# main.net
KiCad netlist of a schematic drawn in Altium Designer
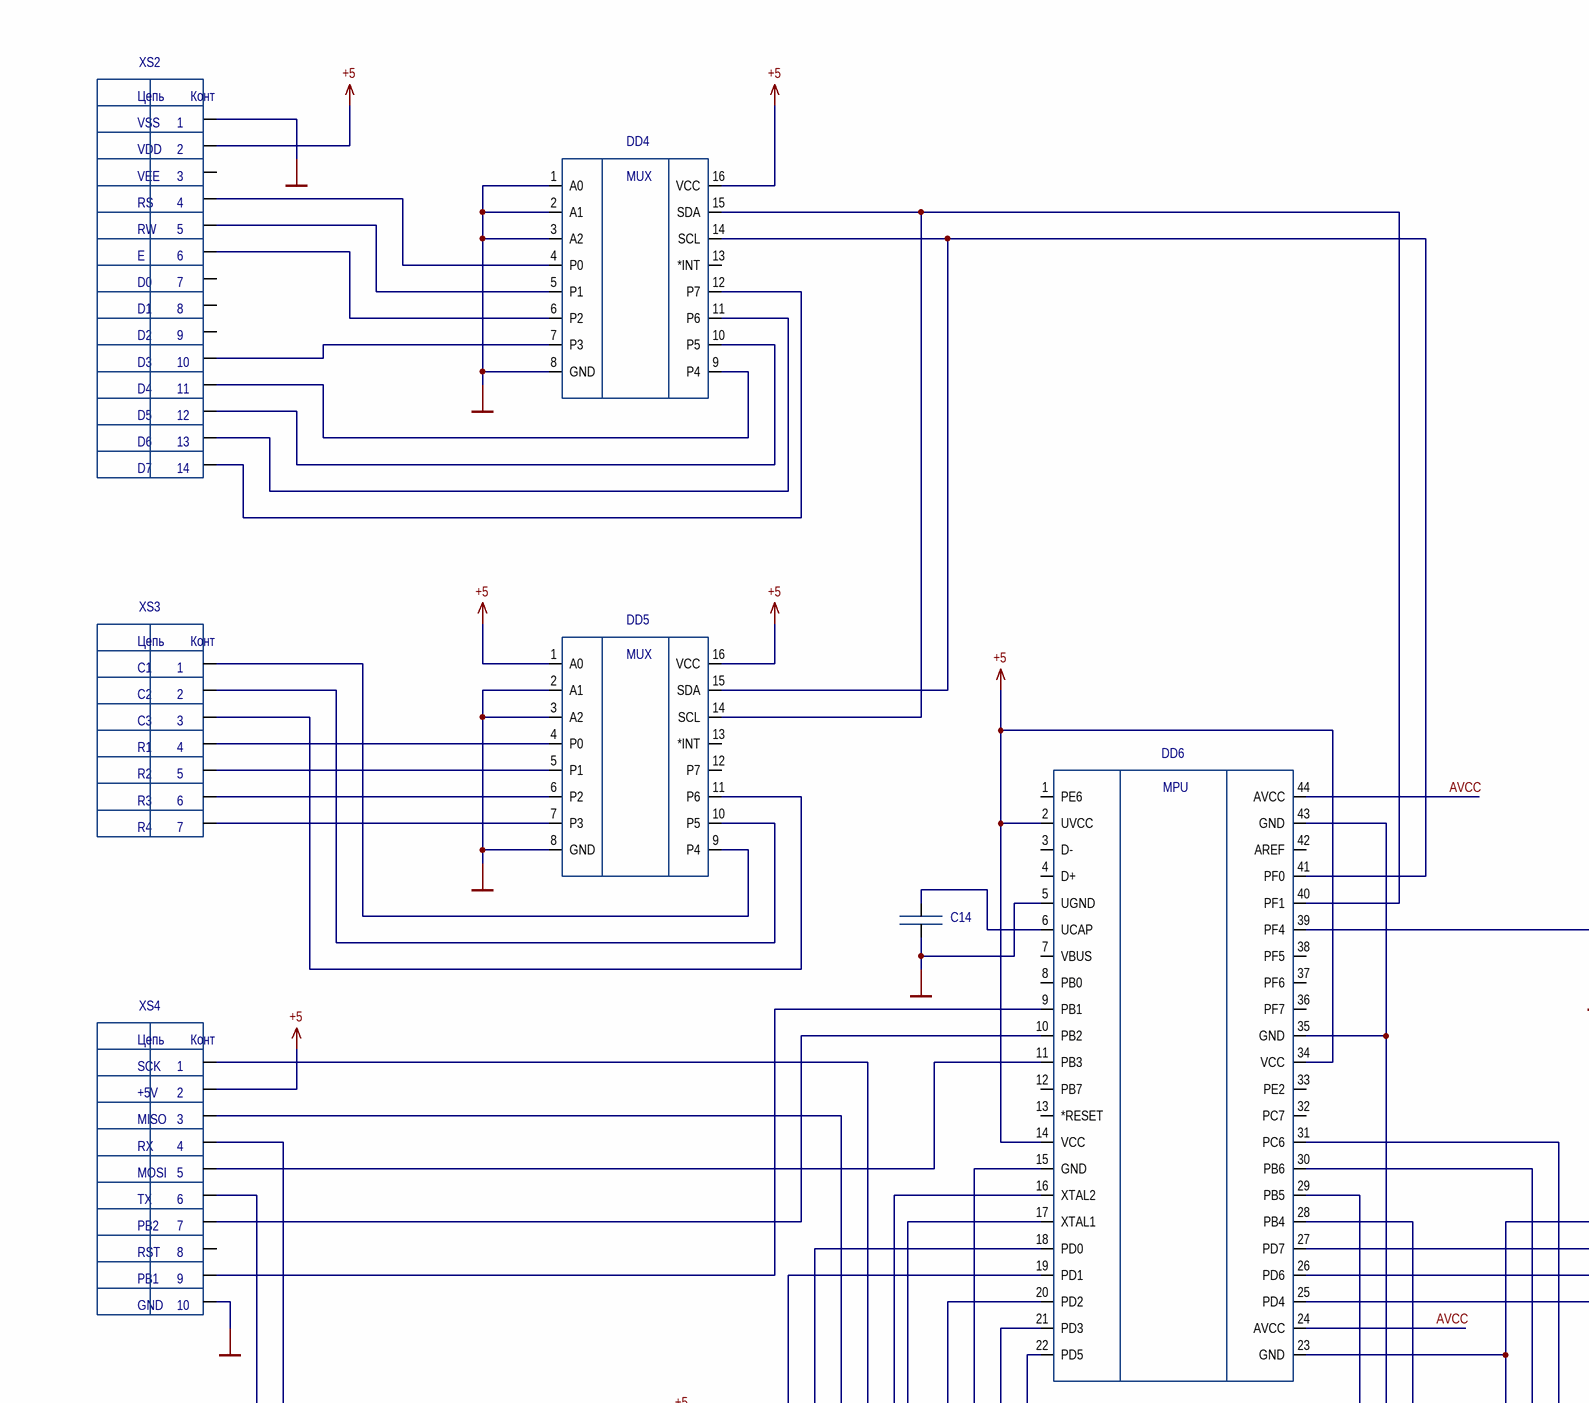
[diagram p0: main.SchDoc, top left]
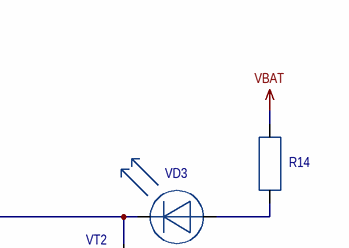
[diagram p1: main.SchDoc, top right]
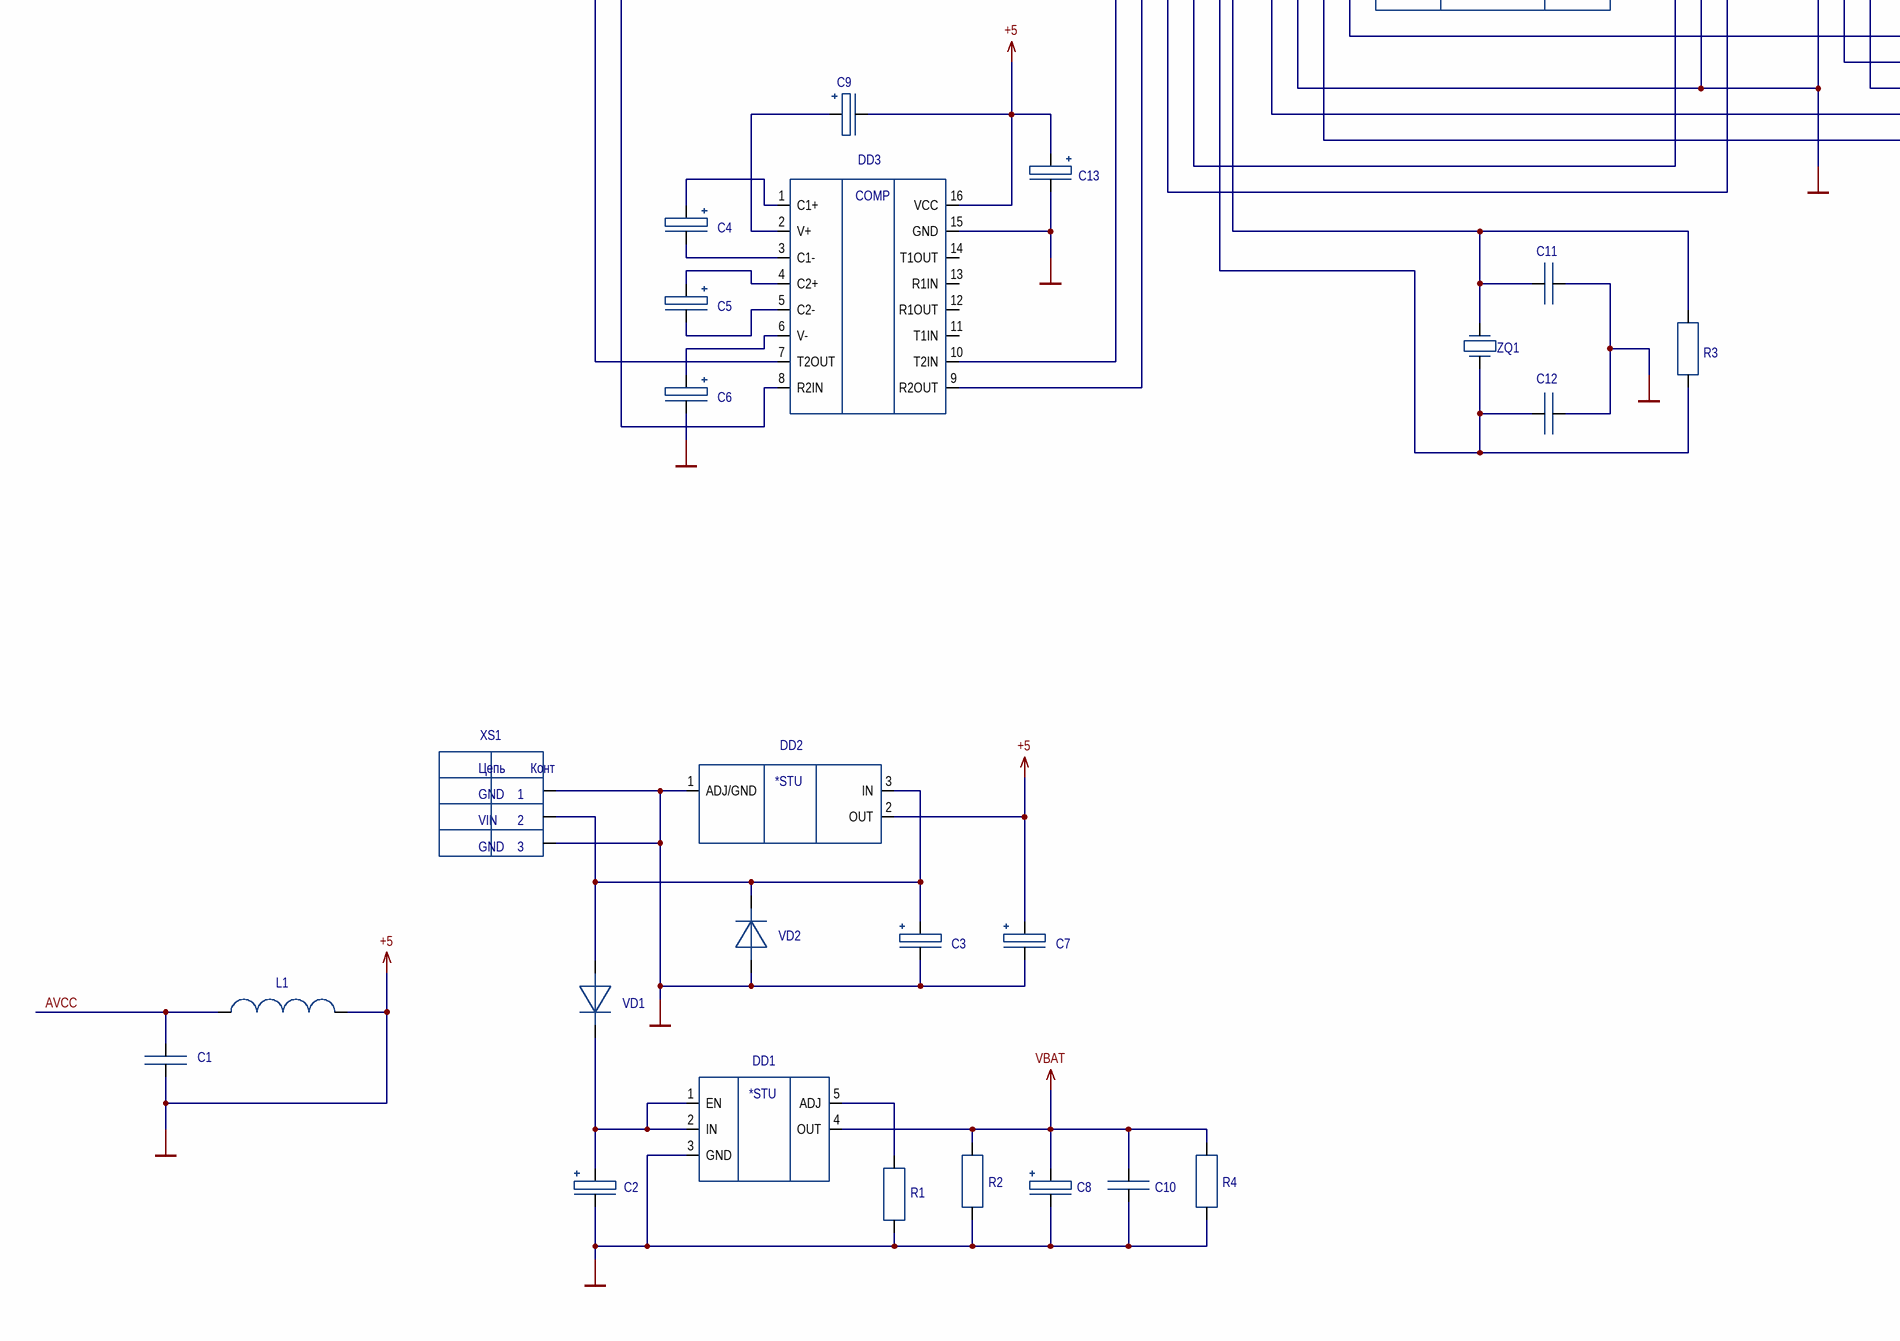
[diagram p2: main.SchDoc, bottom left]
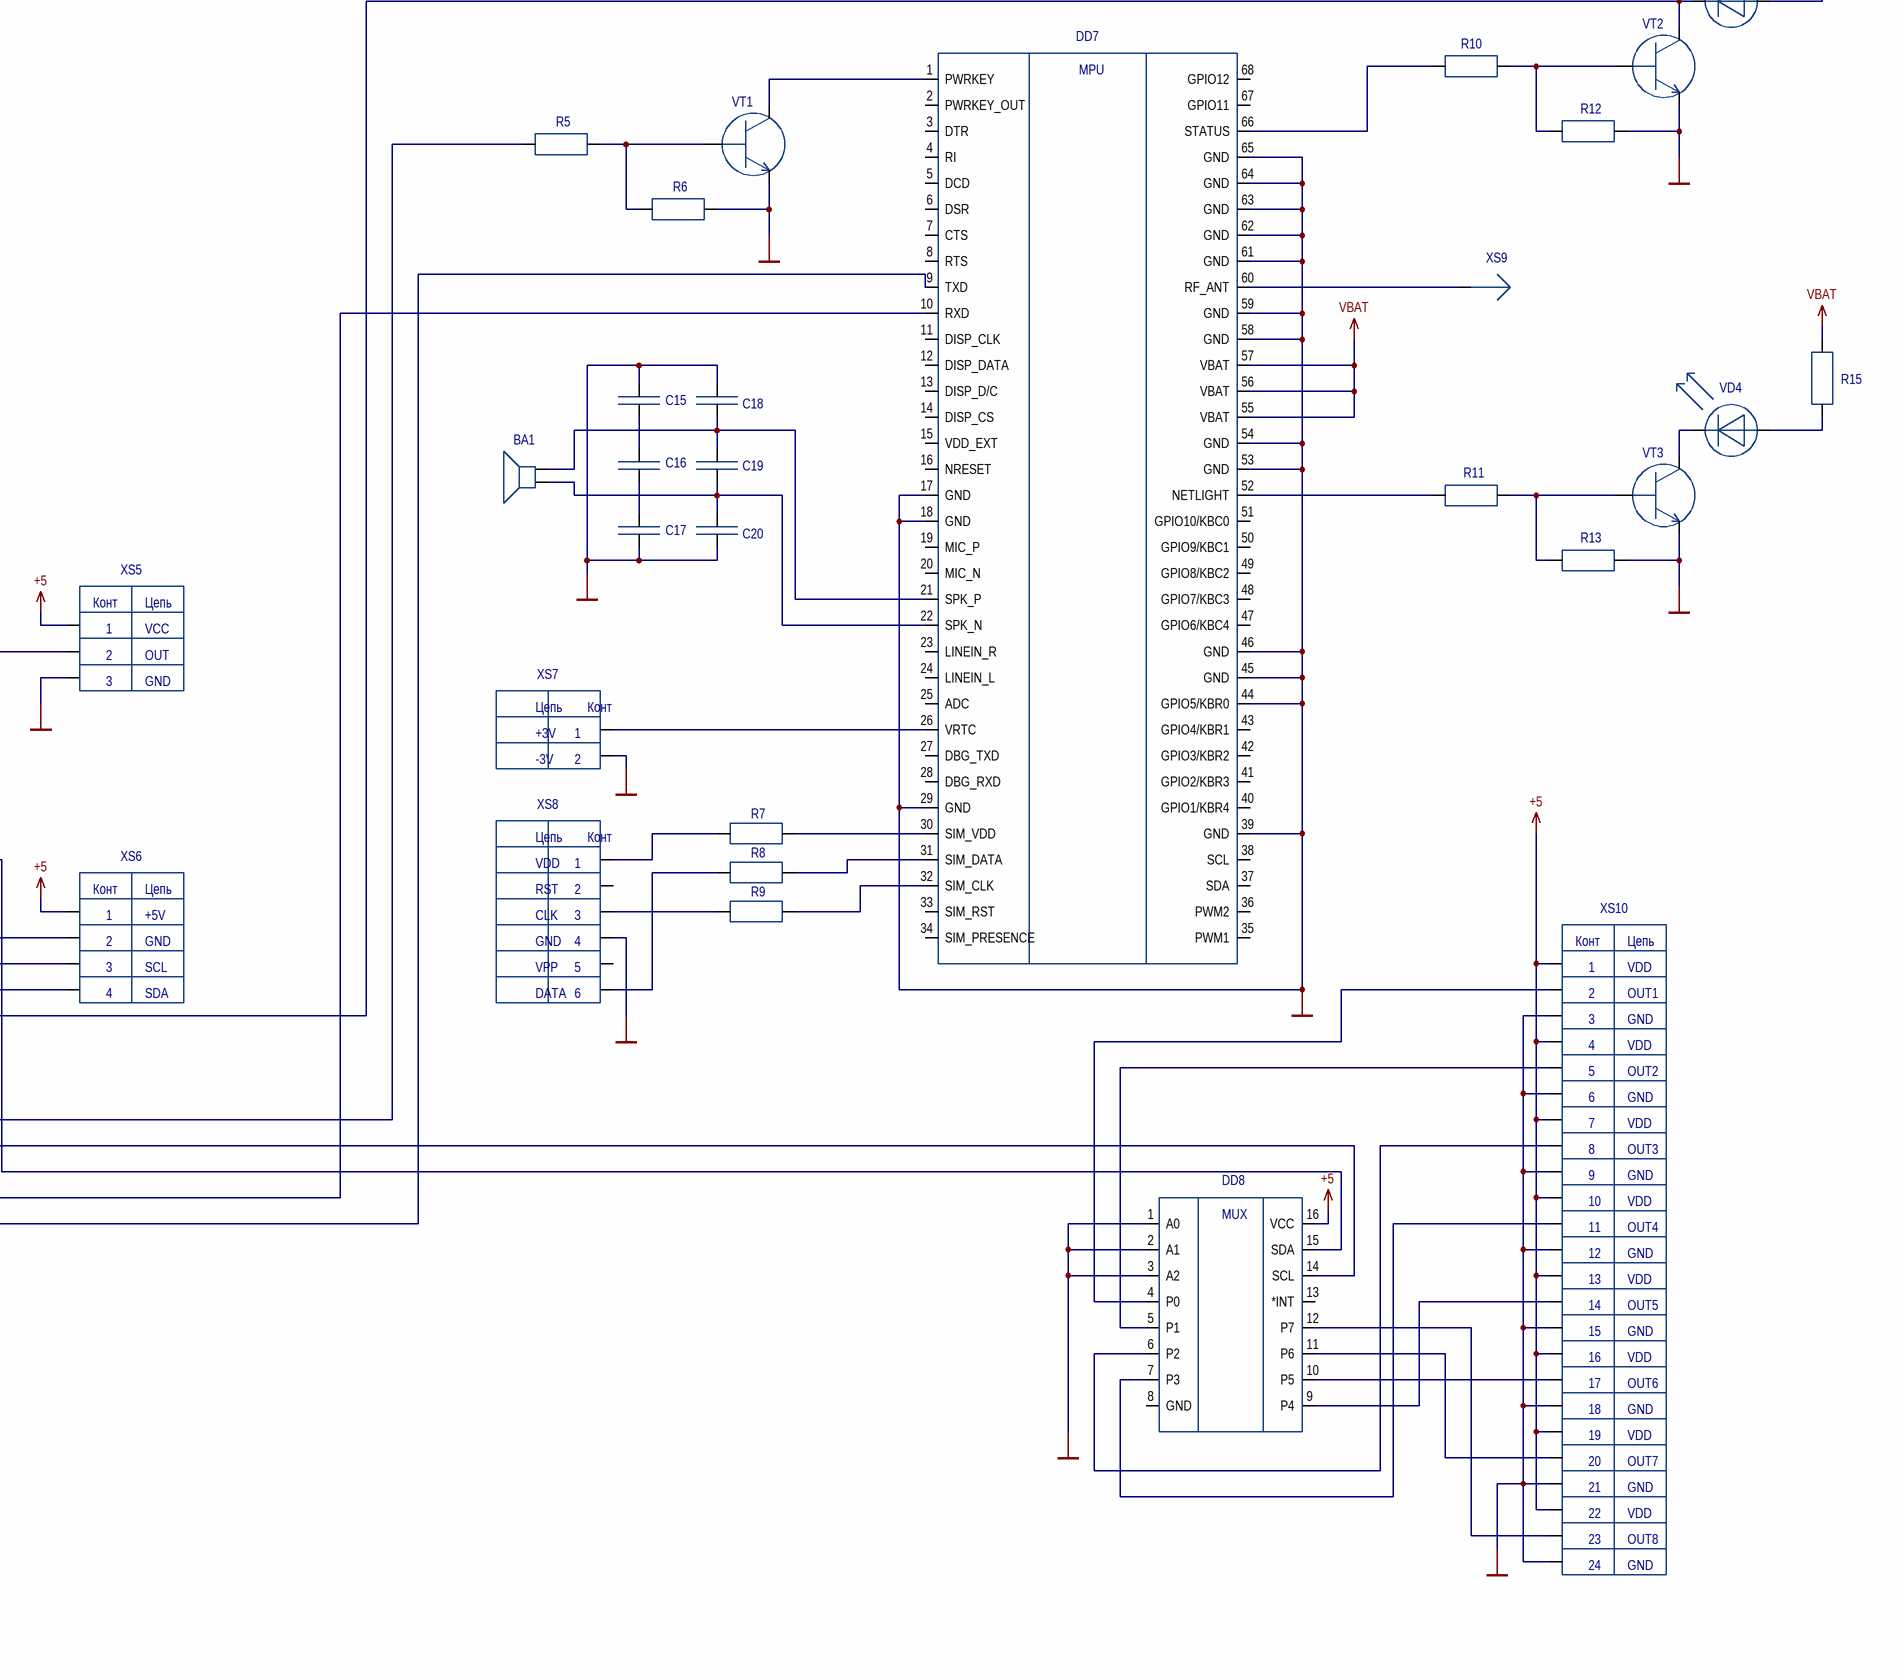
[diagram p3: main.SchDoc, bottom right]

(export (version "E")
  (design (tool "Eeschema 10.0.6"))
  (components
    (comp (ref "BA1")
      (value "speaker_CVS-1508")
      (footprint "diploma:SPeaKeR_CVS-1508")
      (libsource (lib "diploma") (part "speaker_CVS-1508"))
    )
    (comp (ref "C1")
      (value "cap_1mkF")
      (footprint "diploma:CAP_0805_GRM")
      (libsource (lib "diploma") (part "cap_1mkF"))
    )
    (comp (ref "C2")
      (value "cap_pol_100mkF")
      (footprint "diploma:PCAP_10X20_RUB")
      (libsource (lib "diploma") (part "cap_pol_100mkF"))
    )
    (comp (ref "C3")
      (value "pol_10mkF")
      (footprint "diploma:PCAP_6_3x11THRU-ELECT_NCA")
      (libsource (lib "diploma") (part "cap_pol_10mkF"))
    )
    (comp (ref "C4")
      (value "pol_1mkF")
      (footprint "PCAP_5x11-THRU-ELECT_NCA")
      (libsource (lib "diploma") (part "cap_pol_1mkF"))
    )
    (comp (ref "C5")
      (value "pol_1mkF")
      (footprint "PCAP_5x11-THRU-ELECT_NCA")
      (libsource (lib "diploma") (part "cap_pol_1mkF"))
    )
    (comp (ref "C6")
      (value "pol_1mkF")
      (footprint "PCAP_5x11-THRU-ELECT_NCA")
      (libsource (lib "diploma") (part "cap_pol_1mkF"))
    )
    (comp (ref "C7")
      (value "pol_10mkF")
      (footprint "diploma:PCAP_6_3x11THRU-ELECT_NCA")
      (libsource (lib "diploma") (part "cap_pol_10mkF"))
    )
    (comp (ref "C8")
      (value "cap_pol_100mkF")
      (footprint "diploma:PCAP_10X20_RUB")
      (libsource (lib "diploma") (part "cap_pol_100mkF"))
    )
    (comp (ref "C9")
      (value "pol_1mkF")
      (footprint "PCAP_5x11-THRU-ELECT_NCA")
      (libsource (lib "diploma") (part "cap_pol_1mkF"))
    )
    (comp (ref "C10")
      (value "cap_100nF")
      (footprint "diploma:CAP_0805_GRM")
      (libsource (lib "diploma") (part "cap_100nF"))
    )
    (comp (ref "C11")
      (value "33pF")
      (footprint "diploma:CAP_0805_GRM")
      (libsource (lib "diploma") (part "cap_33pF"))
    )
    (comp (ref "C12")
      (value "33pF")
      (footprint "diploma:CAP_0805_GRM")
      (libsource (lib "diploma") (part "cap_33pF"))
    )
    (comp (ref "C13")
      (value "pol_1mkF")
      (footprint "PCAP_5x11-THRU-ELECT_NCA")
      (libsource (lib "diploma") (part "cap_pol_1mkF"))
    )
    (comp (ref "C14")
      (value "cap_1mkF")
      (footprint "diploma:CAP_0805_GRM")
      (libsource (lib "diploma") (part "cap_1mkF"))
    )
    (comp (ref "C15")
      (value "cap_10pF")
      (footprint "CAP_0805_GRM")
      (libsource (lib "diploma") (part "cap_10pF"))
    )
    (comp (ref "C16")
      (value "cap_10pF")
      (footprint "CAP_0805_GRM")
      (libsource (lib "diploma") (part "cap_10pF"))
    )
    (comp (ref "C17")
      (value "cap_10pF")
      (footprint "CAP_0805_GRM")
      (libsource (lib "diploma") (part "cap_10pF"))
    )
    (comp (ref "C18")
      (value "cap_33pF")
      (footprint "diploma:CAP_0805_GRM")
      (libsource (lib "diploma") (part "cap_33pF"))
    )
    (comp (ref "C19")
      (value "cap_33pF")
      (footprint "diploma:CAP_0805_GRM")
      (libsource (lib "diploma") (part "cap_33pF"))
    )
    (comp (ref "C20")
      (value "cap_33pF")
      (footprint "diploma:CAP_0805_GRM")
      (libsource (lib "diploma") (part "cap_33pF"))
    )
    (comp (ref "DD1")
      (value "stu_MIC29302WT")
      (footprint "diploma:TO-263-5_MCH")
      (libsource (lib "diploma") (part "stu_MIC29302WT"))
    )
    (comp (ref "DD2")
      (value "NCP1117ST50T3G")
      (footprint "SOT223-3_ONS")
      (description "No Description Available")
      (fields (field (name "COPYRIGHT") "Copyright (C) 2016 Accelerated Designs. All rights reserved"))
      (libsource (lib "diploma") (part "stu_NCP1117ST50T3G"))
    )
    (comp (ref "DD3")
      (value "MAX232CSE+")
      (footprint "diploma:max232_dip16")
      (description "No Description Available")
      (fields (field (name "COPYRIGHT") "Copyright (C) 2018 Accelerated Designs. All rights reserved"))
      (libsource (lib "diploma") (part "micro_MAX232"))
    )
    (comp (ref "DD4")
      (value "PCF8574AP")
      (footprint "diploma:SOT38-4_NXP")
      (description "No Description Available")
      (fields (field (name "COPYRIGHT") "Copyright (C) 2018 Accelerated Designs. All rights reserved"))
      (libsource (lib "diploma") (part "micro_PCF8574AP"))
    )
    (comp (ref "DD5")
      (value "PCF8574AP")
      (footprint "diploma:SOT38-4_NXP")
      (description "No Description Available")
      (fields (field (name "COPYRIGHT") "Copyright (C) 2018 Accelerated Designs. All rights reserved"))
      (libsource (lib "diploma") (part "micro_PCF8574AP"))
    )
    (comp (ref "DD6")
      (value "ATMEGA32U4RC-AU")
      (footprint "diploma:atmega32u4_44ML_ATM")
      (description "No Description Available")
      (fields (field (name "COPYRIGHT") "Copyright (C) 2018 Accelerated Designs. All rights reserved"))
      (libsource (lib "diploma") (part "micro_ATMEGA32U4"))
    )
    (comp (ref "DD7")
      (value "SIM900A")
      (footprint "diploma:SIM800A_SMM")
      (libsource (lib "diploma") (part "SIM900A"))
    )
    (comp (ref "DD8")
      (value "PCF8574AP")
      (footprint "diploma:SOT38-4_NXP")
      (description "No Description Available")
      (fields (field (name "COPYRIGHT") "Copyright (C) 2018 Accelerated Designs. All rights reserved"))
      (libsource (lib "diploma") (part "micro_PCF8574AP"))
    )
    (comp (ref "L1")
      (value "inductor_10uH")
      (footprint "diploma:IND_EPCOS_B82432A_EPC")
      (libsource (lib "diploma") (part "inductor_10uH"))
    )
    (comp (ref "R1")
      (value "res_47k")
      (footprint "diploma:RC0805N_YAG")
      (libsource (lib "diploma") (part "res_47k"))
    )
    (comp (ref "R2")
      (value "res_100K")
      (footprint "diploma:RC0805N_YAG")
      (libsource (lib "diploma") (part "res_100K"))
    )
    (comp (ref "R3")
      (value "res_1M")
      (footprint "diploma:RC0805N_YAG")
      (libsource (lib "diploma") (part "res_1M"))
    )
    (comp (ref "R4")
      (value "res_510")
      (footprint "diploma:RC0805N_YAG")
      (libsource (lib "diploma") (part "res_510"))
    )
    (comp (ref "R5")
      (value "res_4.7k")
      (footprint "diploma:RC0805N_YAG")
      (libsource (lib "diploma") (part "res_4.7k"))
    )
    (comp (ref "R6")
      (value "res_47k")
      (footprint "diploma:RC0805N_YAG")
      (libsource (lib "") (part "res_47k_1"))
    )
    (comp (ref "R7")
      (value "res_22")
      (footprint "diploma:RC0805N_YAG")
      (libsource (lib "diploma") (part "res_22"))
    )
    (comp (ref "R8")
      (value "res_22")
      (footprint "diploma:RC0805N_YAG")
      (libsource (lib "diploma") (part "res_22"))
    )
    (comp (ref "R9")
      (value "res_22")
      (footprint "diploma:RC0805N_YAG")
      (libsource (lib "diploma") (part "res_22"))
    )
    (comp (ref "R10")
      (value "res_4.7k")
      (footprint "diploma:RC0805N_YAG")
      (libsource (lib "diploma") (part "res_4.7k"))
    )
    (comp (ref "R11")
      (value "res_4.7k")
      (footprint "diploma:RC0805N_YAG")
      (libsource (lib "diploma") (part "res_4.7k"))
    )
    (comp (ref "R12")
      (value "res_47k")
      (footprint "diploma:RC0805N_YAG")
      (libsource (lib "") (part "res_47k_1"))
    )
    (comp (ref "R13")
      (value "res_47k")
      (footprint "diploma:RC0805N_YAG")
      (libsource (lib "") (part "res_47k_1"))
    )
    (comp (ref "R14")
      (value "res_510")
      (footprint "diploma:RC0805N_YAG")
      (libsource (lib "diploma") (part "res_510"))
    )
    (comp (ref "R15")
      (value "res_510")
      (footprint "diploma:RC0805N_YAG")
      (libsource (lib "diploma") (part "res_510"))
    )
    (comp (ref "VD1")
      (value "diode_M7")
      (footprint "diploma:M7_DO-214AC_DTC")
      (libsource (lib "diploma") (part "diode_M7"))
    )
    (comp (ref "VD2")
      (value "diode_M7")
      (footprint "diploma:M7_DO-214AC_DTC")
      (libsource (lib "diploma") (part "diode_M7"))
    )
    (comp (ref "VD3")
      (value "diode_red")
      (footprint "diploma:LED_151054RS03000")
      (libsource (lib "diploma") (part "diode_red"))
    )
    (comp (ref "VD4")
      (value "diode_red")
      (footprint "diploma:LED_151054RS03000")
      (libsource (lib "diploma") (part "diode_red"))
    )
    (comp (ref "VT1")
      (value "BC547A")
      (footprint "diploma:TO-92-3_ONS")
      (libsource (lib "diploma") (part "trans_BC547A"))
    )
    (comp (ref "VT2")
      (value "BC547A")
      (footprint "diploma:TO-92-3_ONS")
      (libsource (lib "diploma") (part "trans_BC547A"))
    )
    (comp (ref "VT3")
      (value "BC547A")
      (footprint "diploma:TO-92-3_ONS")
      (libsource (lib "diploma") (part "trans_BC547A"))
    )
    (comp (ref "XS1")
      (value "DCJ200-10")
      (footprint "diploma:conn_DCJ200-10")
      (libsource (lib "diploma") (part "conn_DCJ200-10_powerIn"))
    )
    (comp (ref "XS2")
      (value "KUIBIAOCHI_14pin_aliexp")
      (footprint "diploma:conn_14pin_TSW-107-05-G-D")
      (libsource (lib "diploma") (part "conn_LCD"))
    )
    (comp (ref "XS3")
      (value "conn_Keypad")
      (footprint "diploma:conn_7pin_TSW-107-05-G-D")
      (libsource (lib "diploma") (part "conn_Keypad"))
    )
    (comp (ref "XS4")
      (value "BH-10")
      (footprint "diploma:conn_10pin_TE_5-102570-3")
      (libsource (lib "diploma") (part "RS-232"))
    )
    (comp (ref "XS5")
      (value "VS1833B_IR_port")
      (footprint "diploma:conn_3pin_TSW-103-05-G-S")
      (libsource (lib "diploma") (part "conn_IR_port"))
    )
    (comp (ref "XS6")
      (value "DS1095 W-R")
      (footprint "diploma:conn_USB-A-S-X-X-SM2")
      (libsource (lib "diploma") (part "conn_usb_typeA"))
    )
    (comp (ref "XS7")
      (value "conn_Battery_CR2032")
      (footprint "diploma:conn_BAT_BH600")
      (libsource (lib "diploma") (part "conn_Battery_CR2032"))
    )
    (comp (ref "XS8")
      (value "SIM7200-6-0-18-00-X_REVA")
      (footprint "CONN_SIM7200-6-0-18-00-X_REVA")
      (description "No Description Available")
      (fields
        (field (name "MANUFACTURER_PART_NUMBER") "SIM5051-6-0-18-00-A")
        (field (name "COPYRIGHT") "Copyright (C) 2018 Accelerated Designs. All rights reserved")
      )
      (libsource (lib "diploma") (part "conn_SIM7200"))
    )
    (comp (ref "XS9")
      (value "antenn_RECE.20279.001E.01")
      (footprint "diploma:conn_antenn_901-9894-RFX")
      (libsource (lib "diploma") (part "conn_antenn"))
    )
    (comp (ref "XS10")
      (value "BH-24")
      (footprint "diploma:conn_24pin_TSW-108-08-T-T")
      (libsource (lib "diploma") (part "conn_24pin_temperature_sensors"))
    )
    (comp (ref "ZQ1")
      (value "crystal_8mhz")
      (footprint "diploma:CRYSTAL_HC49S_MTC")
      (libsource (lib "diploma") (part "crystal_8mhz"))
    )
  )
  (nets
    (net (code "1") (name "+5") (class "Default")
      (node (ref "C1") (pin "1") (pinfunction "1_1") (pintype "passive"))
      (node (ref "C10") (pin "1") (pinfunction "1_1") (pintype "passive"))
      (node (ref "C11") (pin "2") (pinfunction "2_2") (pintype "passive"))
      (node (ref "C12") (pin "2") (pinfunction "2_2") (pintype "passive"))
      (node (ref "C13") (pin "1") (pinfunction "1_1") (pintype "passive"))
      (node (ref "C13") (pin "2") (pinfunction "2_2") (pintype "passive"))
      (node (ref "C15") (pin "2") (pinfunction "2_2") (pintype "passive"))
      (node (ref "C17") (pin "1") (pinfunction "1_1") (pintype "passive"))
      (node (ref "C18") (pin "2") (pinfunction "2_2") (pintype "passive"))
      (node (ref "C2") (pin "1") (pinfunction "1_1") (pintype "passive"))
      (node (ref "C20") (pin "1") (pinfunction "1_1") (pintype "passive"))
      (node (ref "C3") (pin "1") (pinfunction "1_1") (pintype "passive"))
      (node (ref "C6") (pin "1") (pinfunction "1_1") (pintype "passive"))
      (node (ref "C7") (pin "1") (pinfunction "1_1") (pintype "passive"))
      (node (ref "C7") (pin "2") (pinfunction "2_2") (pintype "passive"))
      (node (ref "C8") (pin "1") (pinfunction "1_1") (pintype "passive"))
      (node (ref "C9") (pin "1") (pinfunction "1_1") (pintype "passive"))
      (node (ref "DD1") (pin "3") (pinfunction "GND_3") (pintype "passive"))
      (node (ref "DD2") (pin "1") (pinfunction "ADJ/GND_1") (pintype "passive"))
      (node (ref "DD2") (pin "2") (pinfunction "OUT_2") (pintype "passive"))
      (node (ref "DD3") (pin "15") (pinfunction "GND_15") (pintype "passive"))
      (node (ref "DD3") (pin "16") (pinfunction "VCC_16") (pintype "passive"))
      (node (ref "DD4") (pin "1") (pinfunction "A0_1") (pintype "passive"))
      (node (ref "DD4") (pin "16") (pinfunction "VCC_16") (pintype "passive"))
      (node (ref "DD4") (pin "2") (pinfunction "A1_2") (pintype "passive"))
      (node (ref "DD4") (pin "3") (pinfunction "A2_3") (pintype "passive"))
      (node (ref "DD4") (pin "8") (pinfunction "GND_8") (pintype "passive"))
      (node (ref "DD5") (pin "1") (pinfunction "A0_1") (pintype "passive"))
      (node (ref "DD5") (pin "16") (pinfunction "VCC_16") (pintype "passive"))
      (node (ref "DD5") (pin "2") (pinfunction "A1_2") (pintype "passive"))
      (node (ref "DD5") (pin "3") (pinfunction "A2_3") (pintype "passive"))
      (node (ref "DD5") (pin "8") (pinfunction "GND_8") (pintype "passive"))
      (node (ref "DD6") (pin "14") (pinfunction "VCC_14") (pintype "passive"))
      (node (ref "DD6") (pin "15") (pinfunction "GND_15") (pintype "passive"))
      (node (ref "DD6") (pin "2") (pinfunction "UVCC_2") (pintype "passive"))
      (node (ref "DD6") (pin "23") (pinfunction "GND_23") (pintype "passive"))
      (node (ref "DD6") (pin "34") (pinfunction "VCC_34") (pintype "passive"))
      (node (ref "DD6") (pin "35") (pinfunction "GND_35") (pintype "passive"))
      (node (ref "DD6") (pin "43") (pinfunction "GND_43") (pintype "passive"))
      (node (ref "DD7") (pin "17") (pinfunction "GND_17") (pintype "passive"))
      (node (ref "DD7") (pin "18") (pinfunction "GND_18") (pintype "passive"))
      (node (ref "DD7") (pin "29") (pinfunction "GND_29") (pintype "passive"))
      (node (ref "DD7") (pin "39") (pinfunction "GND_39") (pintype "passive"))
      (node (ref "DD7") (pin "44") (pinfunction "GPIO5/KBR0_44") (pintype "passive"))
      (node (ref "DD7") (pin "45") (pinfunction "GND_45") (pintype "passive"))
      (node (ref "DD7") (pin "46") (pinfunction "GND_46") (pintype "passive"))
      (node (ref "DD7") (pin "53") (pinfunction "GND_53") (pintype "passive"))
      (node (ref "DD7") (pin "54") (pinfunction "GND_54") (pintype "passive"))
      (node (ref "DD7") (pin "58") (pinfunction "GND_58") (pintype "passive"))
      (node (ref "DD7") (pin "59") (pinfunction "GND_59") (pintype "passive"))
      (node (ref "DD7") (pin "61") (pinfunction "GND_61") (pintype "passive"))
      (node (ref "DD7") (pin "62") (pinfunction "GND_62") (pintype "passive"))
      (node (ref "DD7") (pin "63") (pinfunction "GND_63") (pintype "passive"))
      (node (ref "DD7") (pin "64") (pinfunction "GND_64") (pintype "passive"))
      (node (ref "DD7") (pin "65") (pinfunction "GND_65") (pintype "passive"))
      (node (ref "DD8") (pin "1") (pinfunction "A0_1") (pintype "passive"))
      (node (ref "DD8") (pin "16") (pinfunction "VCC_16") (pintype "passive"))
      (node (ref "DD8") (pin "2") (pinfunction "A1_2") (pintype "passive"))
      (node (ref "DD8") (pin "3") (pinfunction "A2_3") (pintype "passive"))
      (node (ref "L1") (pin "2") (pinfunction "2_2") (pintype "passive"))
      (node (ref "R1") (pin "1") (pinfunction "1_1") (pintype "passive"))
      (node (ref "R12") (pin "2") (pinfunction "2_2") (pintype "passive"))
      (node (ref "R13") (pin "2") (pinfunction "2_2") (pintype "passive"))
      (node (ref "R2") (pin "1") (pinfunction "1_1") (pintype "passive"))
      (node (ref "R4") (pin "1") (pinfunction "1_1") (pintype "passive"))
      (node (ref "R6") (pin "2") (pinfunction "2_2") (pintype "passive"))
      (node (ref "VD2") (pin "1") (pinfunction "1_1") (pintype "passive"))
      (node (ref "VT1") (pin "1") (pinfunction "E_1") (pintype "passive"))
      (node (ref "VT2") (pin "1") (pinfunction "E_1") (pintype "passive"))
      (node (ref "VT3") (pin "1") (pinfunction "E_1") (pintype "passive"))
      (node (ref "XS1") (pin "1") (pinfunction "+5V_1") (pintype "passive"))
      (node (ref "XS1") (pin "3") (pinfunction "SCL_3") (pintype "passive"))
      (node (ref "XS10") (pin "1") (pinfunction "VSS_1") (pintype "passive"))
      (node (ref "XS10") (pin "10") (pinfunction "D3_10") (pintype "passive"))
      (node (ref "XS10") (pin "12") (pinfunction "D5_12") (pintype "passive"))
      (node (ref "XS10") (pin "13") (pinfunction "D6_13") (pintype "passive"))
      (node (ref "XS10") (pin "15") (pinfunction "15_15") (pintype "passive"))
      (node (ref "XS10") (pin "16") (pinfunction "16_16") (pintype "passive"))
      (node (ref "XS10") (pin "18") (pinfunction "18_18") (pintype "passive"))
      (node (ref "XS10") (pin "19") (pinfunction "19_19") (pintype "passive"))
      (node (ref "XS10") (pin "21") (pinfunction "21_21") (pintype "passive"))
      (node (ref "XS10") (pin "22") (pinfunction "22_22") (pintype "passive"))
      (node (ref "XS10") (pin "24") (pinfunction "24_24") (pintype "passive"))
      (node (ref "XS10") (pin "3") (pinfunction "VO_3") (pintype "passive"))
      (node (ref "XS10") (pin "4") (pinfunction "C/D_4") (pintype "passive"))
      (node (ref "XS10") (pin "6") (pinfunction "*WR_6") (pintype "passive"))
      (node (ref "XS10") (pin "7") (pinfunction "D0_7") (pintype "passive"))
      (node (ref "XS10") (pin "9") (pinfunction "D2_9") (pintype "passive"))
      (node (ref "XS2") (pin "1") (pinfunction "VSS_1") (pintype "passive"))
      (node (ref "XS2") (pin "2") (pinfunction "VDD_2") (pintype "passive"))
      (node (ref "XS4") (pin "10") (pinfunction "D3_10") (pintype "passive"))
      (node (ref "XS4") (pin "2") (pinfunction "VDD_2") (pintype "passive"))
      (node (ref "XS5") (pin "1") (pinfunction "VCC_1") (pintype "passive"))
      (node (ref "XS5") (pin "3") (pinfunction "GND_3") (pintype "passive"))
      (node (ref "XS6") (pin "1") (pinfunction "+5V_1") (pintype "passive"))
      (node (ref "XS6") (pin "2") (pinfunction "GND_2") (pintype "passive"))
      (node (ref "XS7") (pin "2") (pinfunction "2_2") (pintype "passive"))
      (node (ref "XS8") (pin "4") (pinfunction "GND_4") (pintype "passive"))
    )
    (net (code "2") (name "/AVCC") (class "Default")
      (node (ref "C1") (pin "2") (pinfunction "2_2") (pintype "passive"))
      (node (ref "DD6") (pin "24") (pinfunction "AVCC_24") (pintype "passive"))
      (node (ref "DD6") (pin "44") (pinfunction "AVCC_44") (pintype "passive"))
      (node (ref "L1") (pin "1") (pinfunction "1_1") (pintype "passive"))
    )
    (net (code "3") (name "Net-(C15-Pad1)") (class "Default")
      (node (ref "C15") (pin "1") (pinfunction "1_1") (pintype "passive"))
      (node (ref "C16") (pin "2") (pinfunction "2_2") (pintype "passive"))
    )
    (net (code "4") (name "Net-(C16-Pad1)") (class "Default")
      (node (ref "C16") (pin "1") (pinfunction "1_1") (pintype "passive"))
      (node (ref "C17") (pin "2") (pinfunction "2_2") (pintype "passive"))
    )
    (net (code "5") (name "Net-(DD1-ADJ)") (class "Default")
      (node (ref "DD1") (pin "5") (pinfunction "ADJ_5") (pintype "passive"))
      (node (ref "R1") (pin "2") (pinfunction "2_2") (pintype "passive"))
    )
    (net (code "6") (name "Net-(DD1-EN)") (class "Default")
      (node (ref "C2") (pin "2") (pinfunction "2_2") (pintype "passive"))
      (node (ref "DD1") (pin "1") (pinfunction "EN_1") (pintype "passive"))
      (node (ref "DD1") (pin "2") (pinfunction "IN_2") (pintype "passive"))
      (node (ref "VD1") (pin "2") (pinfunction "2_2") (pintype "passive"))
    )
    (net (code "7") (name "Net-(DD2-IN)") (class "Default")
      (node (ref "C3") (pin "2") (pinfunction "2_2") (pintype "passive"))
      (node (ref "DD2") (pin "3") (pinfunction "IN_3") (pintype "passive"))
      (node (ref "VD1") (pin "1") (pinfunction "1_1") (pintype "passive"))
      (node (ref "VD2") (pin "2") (pinfunction "2_2") (pintype "passive"))
      (node (ref "XS1") (pin "2") (pinfunction "GND_2") (pintype "passive"))
    )
    (net (code "8") (name "Net-(DD3-C1+)") (class "Default")
      (node (ref "C4") (pin "2") (pinfunction "2_2") (pintype "passive"))
      (node (ref "DD3") (pin "1") (pinfunction "C1+_1") (pintype "passive"))
    )
    (net (code "9") (name "Net-(DD3-C1-)") (class "Default")
      (node (ref "C4") (pin "1") (pinfunction "1_1") (pintype "passive"))
      (node (ref "DD3") (pin "3") (pinfunction "C1-_3") (pintype "passive"))
    )
    (net (code "10") (name "Net-(DD3-C2+)") (class "Default")
      (node (ref "C5") (pin "2") (pinfunction "2_2") (pintype "passive"))
      (node (ref "DD3") (pin "4") (pinfunction "C2+_4") (pintype "passive"))
    )
    (net (code "11") (name "Net-(DD3-C2-)") (class "Default")
      (node (ref "C5") (pin "1") (pinfunction "1_1") (pintype "passive"))
      (node (ref "DD3") (pin "5") (pinfunction "C2-_5") (pintype "passive"))
    )
    (net (code "12") (name "Net-(DD3-R2IN)") (class "Default")
      (node (ref "DD3") (pin "8") (pinfunction "R2IN_8") (pintype "passive"))
      (node (ref "XS4") (pin "4") (pinfunction "C/D_4") (pintype "passive"))
    )
    (net (code "13") (name "Net-(DD3-R2OUT)") (class "Default")
      (node (ref "DD3") (pin "9") (pinfunction "R2OUT_9") (pintype "passive"))
      (node (ref "DD6") (pin "18") (pinfunction "PD0_18") (pintype "passive"))
    )
    (net (code "14") (name "Net-(DD3-T2IN)") (class "Default")
      (node (ref "DD3") (pin "10") (pinfunction "T2IN_10") (pintype "passive"))
      (node (ref "DD6") (pin "19") (pinfunction "PD1_19") (pintype "passive"))
    )
    (net (code "15") (name "Net-(DD3-T2OUT)") (class "Default")
      (node (ref "DD3") (pin "7") (pinfunction "T2OUT_7") (pintype "passive"))
      (node (ref "XS4") (pin "6") (pinfunction "*WR_6") (pintype "passive"))
    )
    (net (code "16") (name "Net-(DD3-V+)") (class "Default")
      (node (ref "C9") (pin "2") (pinfunction "2_2") (pintype "passive"))
      (node (ref "DD3") (pin "2") (pinfunction "V+_2") (pintype "passive"))
    )
    (net (code "17") (name "Net-(DD3-V-)") (class "Default")
      (node (ref "C6") (pin "2") (pinfunction "2_2") (pintype "passive"))
      (node (ref "DD3") (pin "6") (pinfunction "V-_6") (pintype "passive"))
    )
    (net (code "18") (name "Net-(DD4-P0)") (class "Default")
      (node (ref "DD4") (pin "4") (pinfunction "P0_4") (pintype "passive"))
      (node (ref "XS2") (pin "4") (pinfunction "C/D_4") (pintype "passive"))
    )
    (net (code "19") (name "Net-(DD4-P1)") (class "Default")
      (node (ref "DD4") (pin "5") (pinfunction "P1_5") (pintype "passive"))
      (node (ref "XS2") (pin "5") (pinfunction "*RD_5") (pintype "passive"))
    )
    (net (code "20") (name "Net-(DD4-P2)") (class "Default")
      (node (ref "DD4") (pin "6") (pinfunction "P2_6") (pintype "passive"))
      (node (ref "XS2") (pin "6") (pinfunction "*WR_6") (pintype "passive"))
    )
    (net (code "21") (name "Net-(DD4-P3)") (class "Default")
      (node (ref "DD4") (pin "7") (pinfunction "P3_7") (pintype "passive"))
      (node (ref "XS2") (pin "10") (pinfunction "D3_10") (pintype "passive"))
    )
    (net (code "22") (name "Net-(DD4-P4)") (class "Default")
      (node (ref "DD4") (pin "9") (pinfunction "P4_9") (pintype "passive"))
      (node (ref "XS2") (pin "11") (pinfunction "D4_11") (pintype "passive"))
    )
    (net (code "23") (name "Net-(DD4-P5)") (class "Default")
      (node (ref "DD4") (pin "10") (pinfunction "P5_10") (pintype "passive"))
      (node (ref "XS2") (pin "12") (pinfunction "D5_12") (pintype "passive"))
    )
    (net (code "24") (name "Net-(DD4-P6)") (class "Default")
      (node (ref "DD4") (pin "11") (pinfunction "P6_11") (pintype "passive"))
      (node (ref "XS2") (pin "13") (pinfunction "D6_13") (pintype "passive"))
    )
    (net (code "25") (name "Net-(DD4-P7)") (class "Default")
      (node (ref "DD4") (pin "12") (pinfunction "P7_12") (pintype "passive"))
      (node (ref "XS2") (pin "14") (pinfunction "D7_14") (pintype "passive"))
    )
    (net (code "26") (name "Net-(DD4-SCL)") (class "Default")
      (node (ref "DD4") (pin "14") (pinfunction "SCL_14") (pintype "passive"))
      (node (ref "DD5") (pin "15") (pinfunction "SDA_15") (pintype "passive"))
      (node (ref "DD6") (pin "41") (pinfunction "PF0_41") (pintype "passive"))
    )
    (net (code "27") (name "Net-(DD4-SDA)") (class "Default")
      (node (ref "DD4") (pin "15") (pinfunction "SDA_15") (pintype "passive"))
      (node (ref "DD5") (pin "14") (pinfunction "SCL_14") (pintype "passive"))
      (node (ref "DD6") (pin "40") (pinfunction "PF1_40") (pintype "passive"))
    )
    (net (code "28") (name "Net-(DD5-P0)") (class "Default")
      (node (ref "DD5") (pin "4") (pinfunction "P0_4") (pintype "passive"))
      (node (ref "XS3") (pin "4") (pinfunction "C/D_4") (pintype "passive"))
    )
    (net (code "29") (name "Net-(DD5-P1)") (class "Default")
      (node (ref "DD5") (pin "5") (pinfunction "P1_5") (pintype "passive"))
      (node (ref "XS3") (pin "5") (pinfunction "*RD_5") (pintype "passive"))
    )
    (net (code "30") (name "Net-(DD5-P2)") (class "Default")
      (node (ref "DD5") (pin "6") (pinfunction "P2_6") (pintype "passive"))
      (node (ref "XS3") (pin "6") (pinfunction "*WR_6") (pintype "passive"))
    )
    (net (code "31") (name "Net-(DD5-P3)") (class "Default")
      (node (ref "DD5") (pin "7") (pinfunction "P3_7") (pintype "passive"))
      (node (ref "XS3") (pin "7") (pinfunction "D0_7") (pintype "passive"))
    )
    (net (code "32") (name "Net-(DD5-P4)") (class "Default")
      (node (ref "DD5") (pin "9") (pinfunction "P4_9") (pintype "passive"))
      (node (ref "XS3") (pin "1") (pinfunction "VSS_1") (pintype "passive"))
    )
    (net (code "33") (name "Net-(DD5-P5)") (class "Default")
      (node (ref "DD5") (pin "10") (pinfunction "P5_10") (pintype "passive"))
      (node (ref "XS3") (pin "2") (pinfunction "VDD_2") (pintype "passive"))
    )
    (net (code "34") (name "Net-(DD5-P6)") (class "Default")
      (node (ref "DD5") (pin "11") (pinfunction "P6_11") (pintype "passive"))
      (node (ref "XS3") (pin "3") (pinfunction "VO_3") (pintype "passive"))
    )
    (net (code "35") (name "Net-(DD6-PB1)") (class "Default")
      (node (ref "DD6") (pin "9") (pinfunction "PB1_9") (pintype "passive"))
      (node (ref "XS4") (pin "9") (pinfunction "D2_9") (pintype "passive"))
    )
    (net (code "36") (name "Net-(DD6-PB2)") (class "Default")
      (node (ref "DD6") (pin "10") (pinfunction "PB2_10") (pintype "passive"))
      (node (ref "XS4") (pin "7") (pinfunction "D0_7") (pintype "passive"))
    )
    (net (code "37") (name "Net-(DD6-PB3)") (class "Default")
      (node (ref "DD6") (pin "11") (pinfunction "PB3_11") (pintype "passive"))
      (node (ref "XS4") (pin "5") (pinfunction "*RD_5") (pintype "passive"))
    )
    (net (code "38") (name "Net-(DD6-PB4)") (class "Default")
      (node (ref "DD6") (pin "28") (pinfunction "PB4_28") (pintype "passive"))
      (node (ref "XS4") (pin "3") (pinfunction "VO_3") (pintype "passive"))
    )
    (net (code "39") (name "Net-(DD6-PB5)") (class "Default")
      (node (ref "DD6") (pin "29") (pinfunction "PB5_29") (pintype "passive"))
      (node (ref "XS4") (pin "1") (pinfunction "VSS_1") (pintype "passive"))
    )
    (net (code "40") (name "Net-(DD6-PB6)") (class "Default")
      (node (ref "DD6") (pin "30") (pinfunction "PB6_30") (pintype "passive"))
      (node (ref "DD8") (pin "14") (pinfunction "SCL_14") (pintype "passive"))
    )
    (net (code "41") (name "Net-(DD6-PC6)") (class "Default")
      (node (ref "DD6") (pin "31") (pinfunction "PC6_31") (pintype "passive"))
      (node (ref "DD8") (pin "15") (pinfunction "SDA_15") (pintype "passive"))
    )
    (net (code "42") (name "Net-(DD6-PD2)") (class "Default")
      (node (ref "DD6") (pin "20") (pinfunction "PD2_20") (pintype "passive"))
      (node (ref "DD7") (pin "10") (pinfunction "RXD_10") (pintype "passive"))
    )
    (net (code "43") (name "Net-(DD6-PD3)") (class "Default")
      (node (ref "DD6") (pin "21") (pinfunction "PD3_21") (pintype "passive"))
      (node (ref "DD7") (pin "9") (pinfunction "TXD_9") (pintype "passive"))
    )
    (net (code "44") (name "Net-(DD6-PD4)") (class "Default")
      (node (ref "DD6") (pin "25") (pinfunction "PD4_25") (pintype "passive"))
      (node (ref "VD3") (pin "2") (pinfunction "2_2") (pintype "passive"))
      (node (ref "VT2") (pin "3") (pinfunction "C_3") (pintype "passive"))
    )
    (net (code "45") (name "Net-(DD6-PD5)") (class "Default")
      (node (ref "DD6") (pin "22") (pinfunction "PD5_22") (pintype "passive"))
      (node (ref "R5") (pin "1") (pinfunction "1_1") (pintype "passive"))
    )
    (net (code "46") (name "Net-(DD6-PD6)") (class "Default")
      (node (ref "DD6") (pin "26") (pinfunction "PD6_26") (pintype "passive"))
      (node (ref "XS6") (pin "4") (pinfunction "SDA_4") (pintype "passive"))
    )
    (net (code "47") (name "Net-(DD6-PD7)") (class "Default")
      (node (ref "DD6") (pin "27") (pinfunction "PD7_27") (pintype "passive"))
      (node (ref "XS6") (pin "3") (pinfunction "SCL_3") (pintype "passive"))
    )
    (net (code "48") (name "Net-(DD6-PF4)") (class "Default")
      (node (ref "DD6") (pin "39") (pinfunction "PF4_39") (pintype "passive"))
      (node (ref "XS5") (pin "2") (pinfunction "OUT_2") (pintype "passive"))
    )
    (net (code "49") (name "Net-(DD6-UCAP)") (class "Default")
      (node (ref "C14") (pin "2") (pinfunction "2_2") (pintype "passive"))
      (node (ref "DD6") (pin "6") (pinfunction "UCAP_6") (pintype "passive"))
    )
    (net (code "50") (name "Net-(DD6-XTAL1)") (class "Default")
      (node (ref "C11") (pin "1") (pinfunction "1_1") (pintype "passive"))
      (node (ref "DD6") (pin "17") (pinfunction "XTAL1_17") (pintype "passive"))
      (node (ref "R3") (pin "2") (pinfunction "2_2") (pintype "passive"))
      (node (ref "ZQ1") (pin "2") (pinfunction "2_2") (pintype "passive"))
    )
    (net (code "51") (name "Net-(DD6-XTAL2)") (class "Default")
      (node (ref "C12") (pin "1") (pinfunction "1_1") (pintype "passive"))
      (node (ref "DD6") (pin "16") (pinfunction "XTAL2_16") (pintype "passive"))
      (node (ref "R3") (pin "1") (pinfunction "1_1") (pintype "passive"))
      (node (ref "ZQ1") (pin "1") (pinfunction "1_1") (pintype "passive"))
    )
    (net (code "52") (name "Net-(DD7-NETLIGHT)") (class "Default")
      (node (ref "DD7") (pin "52") (pinfunction "NETLIGHT_52") (pintype "passive"))
      (node (ref "R11") (pin "1") (pinfunction "1_1") (pintype "passive"))
    )
    (net (code "53") (name "Net-(DD7-PWRKEY)") (class "Default")
      (node (ref "DD7") (pin "1") (pinfunction "PWRKEY_1") (pintype "passive"))
      (node (ref "VT1") (pin "3") (pinfunction "C_3") (pintype "passive"))
    )
    (net (code "54") (name "Net-(DD7-RF_ANT)") (class "Default")
      (node (ref "DD7") (pin "60") (pinfunction "RF_ANT_60") (pintype "passive"))
      (node (ref "XS9") (pin "1") (pinfunction "1_1") (pintype "passive"))
    )
    (net (code "55") (name "Net-(DD7-SIM_CLK)") (class "Default")
      (node (ref "DD7") (pin "32") (pinfunction "SIM_CLK_32") (pintype "passive"))
      (node (ref "R9") (pin "2") (pinfunction "2_2") (pintype "passive"))
    )
    (net (code "56") (name "Net-(DD7-SIM_DATA)") (class "Default")
      (node (ref "DD7") (pin "31") (pinfunction "SIM_DATA_31") (pintype "passive"))
      (node (ref "R8") (pin "2") (pinfunction "2_2") (pintype "passive"))
    )
    (net (code "57") (name "Net-(DD7-SIM_VDD)") (class "Default")
      (node (ref "DD7") (pin "30") (pinfunction "SIM_VDD_30") (pintype "passive"))
      (node (ref "R7") (pin "2") (pinfunction "2_2") (pintype "passive"))
    )
    (net (code "58") (name "Net-(DD7-SPK_N)") (class "Default")
      (node (ref "BA1") (pin "1") (pinfunction "1_1") (pintype "passive"))
      (node (ref "C19") (pin "1") (pinfunction "1_1") (pintype "passive"))
      (node (ref "C20") (pin "2") (pinfunction "2_2") (pintype "passive"))
      (node (ref "DD7") (pin "22") (pinfunction "SPK_N_22") (pintype "passive"))
    )
    (net (code "59") (name "Net-(DD7-SPK_P)") (class "Default")
      (node (ref "BA1") (pin "2") (pinfunction "2_2") (pintype "passive"))
      (node (ref "C18") (pin "1") (pinfunction "1_1") (pintype "passive"))
      (node (ref "C19") (pin "2") (pinfunction "2_2") (pintype "passive"))
      (node (ref "DD7") (pin "21") (pinfunction "SPK_P_21") (pintype "passive"))
    )
    (net (code "60") (name "Net-(DD7-STATUS)") (class "Default")
      (node (ref "DD7") (pin "66") (pinfunction "STATUS_66") (pintype "passive"))
      (node (ref "R10") (pin "1") (pinfunction "1_1") (pintype "passive"))
    )
    (net (code "61") (name "Net-(DD7-VRTC)") (class "Default")
      (node (ref "DD7") (pin "26") (pinfunction "VRTC_26") (pintype "passive"))
      (node (ref "XS7") (pin "1") (pinfunction "VCC_1") (pintype "passive"))
    )
    (net (code "62") (name "Net-(DD8-P0)") (class "Default")
      (node (ref "DD8") (pin "4") (pinfunction "P0_4") (pintype "passive"))
      (node (ref "XS10") (pin "2") (pinfunction "VDD_2") (pintype "passive"))
    )
    (net (code "63") (name "Net-(DD8-P1)") (class "Default")
      (node (ref "DD8") (pin "5") (pinfunction "P1_5") (pintype "passive"))
      (node (ref "XS10") (pin "5") (pinfunction "*RD_5") (pintype "passive"))
    )
    (net (code "64") (name "Net-(DD8-P2)") (class "Default")
      (node (ref "DD8") (pin "6") (pinfunction "P2_6") (pintype "passive"))
      (node (ref "XS10") (pin "8") (pinfunction "D1_8") (pintype "passive"))
    )
    (net (code "65") (name "Net-(DD8-P3)") (class "Default")
      (node (ref "DD8") (pin "7") (pinfunction "P3_7") (pintype "passive"))
      (node (ref "XS10") (pin "11") (pinfunction "D4_11") (pintype "passive"))
    )
    (net (code "66") (name "Net-(DD8-P4)") (class "Default")
      (node (ref "DD8") (pin "9") (pinfunction "P4_9") (pintype "passive"))
      (node (ref "XS10") (pin "14") (pinfunction "D7_14") (pintype "passive"))
    )
    (net (code "67") (name "Net-(DD8-P5)") (class "Default")
      (node (ref "DD8") (pin "10") (pinfunction "P5_10") (pintype "passive"))
      (node (ref "XS10") (pin "17") (pinfunction "17_17") (pintype "passive"))
    )
    (net (code "68") (name "Net-(DD8-P6)") (class "Default")
      (node (ref "DD8") (pin "11") (pinfunction "P6_11") (pintype "passive"))
      (node (ref "XS10") (pin "20") (pinfunction "20_20") (pintype "passive"))
    )
    (net (code "69") (name "Net-(DD8-P7)") (class "Default")
      (node (ref "DD8") (pin "12") (pinfunction "P7_12") (pintype "passive"))
      (node (ref "XS10") (pin "23") (pinfunction "23_23") (pintype "passive"))
    )
    (net (code "70") (name "Net-(R14-Pad1)") (class "Default")
      (node (ref "R14") (pin "1") (pinfunction "1_1") (pintype "passive"))
      (node (ref "VD3") (pin "1") (pinfunction "1_1") (pintype "passive"))
    )
    (net (code "71") (name "Net-(R15-Pad1)") (class "Default")
      (node (ref "R15") (pin "1") (pinfunction "1_1") (pintype "passive"))
      (node (ref "VD4") (pin "1") (pinfunction "1_1") (pintype "passive"))
    )
    (net (code "72") (name "Net-(VT1-B)") (class "Default")
      (node (ref "R5") (pin "2") (pinfunction "2_2") (pintype "passive"))
      (node (ref "R6") (pin "1") (pinfunction "1_1") (pintype "passive"))
      (node (ref "VT1") (pin "2") (pinfunction "B_2") (pintype "passive"))
    )
    (net (code "73") (name "Net-(VT2-B)") (class "Default")
      (node (ref "R10") (pin "2") (pinfunction "2_2") (pintype "passive"))
      (node (ref "R12") (pin "1") (pinfunction "1_1") (pintype "passive"))
      (node (ref "VT2") (pin "2") (pinfunction "B_2") (pintype "passive"))
    )
    (net (code "74") (name "Net-(VT3-B)") (class "Default")
      (node (ref "R11") (pin "2") (pinfunction "2_2") (pintype "passive"))
      (node (ref "R13") (pin "1") (pinfunction "1_1") (pintype "passive"))
      (node (ref "VT3") (pin "2") (pinfunction "B_2") (pintype "passive"))
    )
    (net (code "75") (name "Net-(VT3-C)") (class "Default")
      (node (ref "VD4") (pin "2") (pinfunction "2_2") (pintype "passive"))
      (node (ref "VT3") (pin "3") (pinfunction "C_3") (pintype "passive"))
    )
    (net (code "76") (name "Net-(XS8-CLK)") (class "Default")
      (node (ref "R9") (pin "1") (pinfunction "1_1") (pintype "passive"))
      (node (ref "XS8") (pin "3") (pinfunction "CLK_3") (pintype "passive"))
    )
    (net (code "77") (name "Net-(XS8-I{slash}O)") (class "Default")
      (node (ref "R8") (pin "1") (pinfunction "1_1") (pintype "passive"))
      (node (ref "XS8") (pin "6") (pinfunction "I/O_6") (pintype "passive"))
    )
    (net (code "78") (name "Net-(XS8-VCC)") (class "Default")
      (node (ref "R7") (pin "1") (pinfunction "1_1") (pintype "passive"))
      (node (ref "XS8") (pin "1") (pinfunction "VCC_1") (pintype "power_in"))
    )
    (net (code "79") (name "UGND") (class "Default")
      (node (ref "C14") (pin "1") (pinfunction "1_1") (pintype "passive"))
      (node (ref "DD6") (pin "5") (pinfunction "UGND_5") (pintype "passive"))
    )
    (net (code "80") (name "VBAT") (class "Default")
      (node (ref "C10") (pin "2") (pinfunction "2_2") (pintype "passive"))
      (node (ref "C8") (pin "2") (pinfunction "2_2") (pintype "passive"))
      (node (ref "DD1") (pin "4") (pinfunction "OUT_4") (pintype "passive"))
      (node (ref "DD7") (pin "55") (pinfunction "VBAT_55") (pintype "passive"))
      (node (ref "DD7") (pin "56") (pinfunction "VBAT_56") (pintype "passive"))
      (node (ref "DD7") (pin "57") (pinfunction "VBAT_57") (pintype "passive"))
      (node (ref "R14") (pin "2") (pinfunction "2_2") (pintype "passive"))
      (node (ref "R15") (pin "2") (pinfunction "2_2") (pintype "passive"))
      (node (ref "R2") (pin "2") (pinfunction "2_2") (pintype "passive"))
      (node (ref "R4") (pin "2") (pinfunction "2_2") (pintype "passive"))
    )
    (net (code "81") (name "unconnected-(DD3-R1IN-Pad13)") (class "Default")
      (node (ref "DD3") (pin "13") (pinfunction "R1IN_13") (pintype "passive"))
    )
    (net (code "82") (name "unconnected-(DD3-R1OUT-Pad12)") (class "Default")
      (node (ref "DD3") (pin "12") (pinfunction "R1OUT_12") (pintype "passive"))
    )
    (net (code "83") (name "unconnected-(DD3-T1IN-Pad11)") (class "Default")
      (node (ref "DD3") (pin "11") (pinfunction "T1IN_11") (pintype "passive"))
    )
    (net (code "84") (name "unconnected-(DD3-T1OUT-Pad14)") (class "Default")
      (node (ref "DD3") (pin "14") (pinfunction "T1OUT_14") (pintype "passive"))
    )
    (net (code "85") (name "unconnected-(DD4-*INT-Pad13)") (class "Default")
      (node (ref "DD4") (pin "13") (pinfunction "*INT_13") (pintype "passive"))
    )
    (net (code "86") (name "unconnected-(DD5-*INT-Pad13)") (class "Default")
      (node (ref "DD5") (pin "13") (pinfunction "*INT_13") (pintype "passive"))
    )
    (net (code "87") (name "unconnected-(DD5-P7-Pad12)") (class "Default")
      (node (ref "DD5") (pin "12") (pinfunction "P7_12") (pintype "passive"))
    )
    (net (code "88") (name "unconnected-(DD6-*RESET-Pad13)") (class "Default")
      (node (ref "DD6") (pin "13") (pinfunction "*RESET_13") (pintype "passive"))
    )
    (net (code "89") (name "unconnected-(DD6-AREF-Pad42)") (class "Default")
      (node (ref "DD6") (pin "42") (pinfunction "AREF_42") (pintype "passive"))
    )
    (net (code "90") (name "unconnected-(DD6-D+-Pad4)") (class "Default")
      (node (ref "DD6") (pin "4") (pinfunction "D+_4") (pintype "passive"))
    )
    (net (code "91") (name "unconnected-(DD6-D--Pad3)") (class "Default")
      (node (ref "DD6") (pin "3") (pinfunction "D-_3") (pintype "passive"))
    )
    (net (code "92") (name "unconnected-(DD6-PB0-Pad8)") (class "Default")
      (node (ref "DD6") (pin "8") (pinfunction "PB0_8") (pintype "passive"))
    )
    (net (code "93") (name "unconnected-(DD6-PB7-Pad12)") (class "Default")
      (node (ref "DD6") (pin "12") (pinfunction "PB7_12") (pintype "passive"))
    )
    (net (code "94") (name "unconnected-(DD6-PC7-Pad32)") (class "Default")
      (node (ref "DD6") (pin "32") (pinfunction "PC7_32") (pintype "passive"))
    )
    (net (code "95") (name "unconnected-(DD6-PE2-Pad33)") (class "Default")
      (node (ref "DD6") (pin "33") (pinfunction "PE2_33") (pintype "passive"))
    )
    (net (code "96") (name "unconnected-(DD6-PE6-Pad1)") (class "Default")
      (node (ref "DD6") (pin "1") (pinfunction "PE6_1") (pintype "passive"))
    )
    (net (code "97") (name "unconnected-(DD6-PF5-Pad38)") (class "Default")
      (node (ref "DD6") (pin "38") (pinfunction "PF5_38") (pintype "passive"))
    )
    (net (code "98") (name "unconnected-(DD6-PF6-Pad37)") (class "Default")
      (node (ref "DD6") (pin "37") (pinfunction "PF6_37") (pintype "passive"))
    )
    (net (code "99") (name "unconnected-(DD6-PF7-Pad36)") (class "Default")
      (node (ref "DD6") (pin "36") (pinfunction "PF7_36") (pintype "passive"))
    )
    (net (code "100") (name "unconnected-(DD6-VBUS-Pad7)") (class "Default")
      (node (ref "DD6") (pin "7") (pinfunction "VBUS_7") (pintype "passive"))
    )
    (net (code "101") (name "unconnected-(DD7-ADC-Pad25)") (class "Default")
      (node (ref "DD7") (pin "25") (pinfunction "ADC_25") (pintype "passive"))
    )
    (net (code "102") (name "unconnected-(DD7-CTS-Pad7)") (class "Default")
      (node (ref "DD7") (pin "7") (pinfunction "CTS_7") (pintype "passive"))
    )
    (net (code "103") (name "unconnected-(DD7-DBG_RXD-Pad28)") (class "Default")
      (node (ref "DD7") (pin "28") (pinfunction "DBG_RXD_28") (pintype "passive"))
    )
    (net (code "104") (name "unconnected-(DD7-DBG_TXD-Pad27)") (class "Default")
      (node (ref "DD7") (pin "27") (pinfunction "DBG_TXD_27") (pintype "passive"))
    )
    (net (code "105") (name "unconnected-(DD7-DCD-Pad5)") (class "Default")
      (node (ref "DD7") (pin "5") (pinfunction "DCD_5") (pintype "passive"))
    )
    (net (code "106") (name "unconnected-(DD7-DISP_CLK-Pad11)") (class "Default")
      (node (ref "DD7") (pin "11") (pinfunction "DISP_CLK_11") (pintype "passive"))
    )
    (net (code "107") (name "unconnected-(DD7-DISP_CS-Pad14)") (class "Default")
      (node (ref "DD7") (pin "14") (pinfunction "DISP_CS_14") (pintype "passive"))
    )
    (net (code "108") (name "unconnected-(DD7-DISP_DATA-Pad12)") (class "Default")
      (node (ref "DD7") (pin "12") (pinfunction "DISP_DATA_12") (pintype "passive"))
    )
    (net (code "109") (name "unconnected-(DD7-DISP_D{slash}C-Pad13)") (class "Default")
      (node (ref "DD7") (pin "13") (pinfunction "DISP_D/C_13") (pintype "passive"))
    )
    (net (code "110") (name "unconnected-(DD7-DSR-Pad6)") (class "Default")
      (node (ref "DD7") (pin "6") (pinfunction "DSR_6") (pintype "passive"))
    )
    (net (code "111") (name "unconnected-(DD7-DTR-Pad3)") (class "Default")
      (node (ref "DD7") (pin "3") (pinfunction "DTR_3") (pintype "passive"))
    )
    (net (code "112") (name "unconnected-(DD7-GPIO1{slash}KBR4-Pad40)") (class "Default")
      (node (ref "DD7") (pin "40") (pinfunction "GPIO1/KBR4_40") (pintype "passive"))
    )
    (net (code "113") (name "unconnected-(DD7-GPIO2{slash}KBR3-Pad41)") (class "Default")
      (node (ref "DD7") (pin "41") (pinfunction "GPIO2/KBR3_41") (pintype "passive"))
    )
    (net (code "114") (name "unconnected-(DD7-GPIO3{slash}KBR2-Pad42)") (class "Default")
      (node (ref "DD7") (pin "42") (pinfunction "GPIO3/KBR2_42") (pintype "passive"))
    )
    (net (code "115") (name "unconnected-(DD7-GPIO4{slash}KBR1-Pad43)") (class "Default")
      (node (ref "DD7") (pin "43") (pinfunction "GPIO4/KBR1_43") (pintype "passive"))
    )
    (net (code "116") (name "unconnected-(DD7-GPIO6{slash}KBC4-Pad47)") (class "Default")
      (node (ref "DD7") (pin "47") (pinfunction "GPIO6/KBC4_47") (pintype "passive"))
    )
    (net (code "117") (name "unconnected-(DD7-GPIO7{slash}KBC3-Pad48)") (class "Default")
      (node (ref "DD7") (pin "48") (pinfunction "GPIO7/KBC3_48") (pintype "passive"))
    )
    (net (code "118") (name "unconnected-(DD7-GPIO8{slash}KBC2-Pad49)") (class "Default")
      (node (ref "DD7") (pin "49") (pinfunction "GPIO8/KBC2_49") (pintype "passive"))
    )
    (net (code "119") (name "unconnected-(DD7-GPIO9{slash}KBC1-Pad50)") (class "Default")
      (node (ref "DD7") (pin "50") (pinfunction "GPIO9/KBC1_50") (pintype "passive"))
    )
    (net (code "120") (name "unconnected-(DD7-GPIO10{slash}KBC0-Pad51)") (class "Default")
      (node (ref "DD7") (pin "51") (pinfunction "GPIO10/KBC0_51") (pintype "passive"))
    )
    (net (code "121") (name "unconnected-(DD7-GPIO11-Pad67)") (class "Default")
      (node (ref "DD7") (pin "67") (pinfunction "GPIO11_67") (pintype "passive"))
    )
    (net (code "122") (name "unconnected-(DD7-GPIO12-Pad68)") (class "Default")
      (node (ref "DD7") (pin "68") (pinfunction "GPIO12_68") (pintype "passive"))
    )
    (net (code "123") (name "unconnected-(DD7-LINEIN_L-Pad24)") (class "Default")
      (node (ref "DD7") (pin "24") (pinfunction "LINEIN_L_24") (pintype "passive"))
    )
    (net (code "124") (name "unconnected-(DD7-LINEIN_R-Pad23)") (class "Default")
      (node (ref "DD7") (pin "23") (pinfunction "LINEIN_R_23") (pintype "passive"))
    )
    (net (code "125") (name "unconnected-(DD7-MIC_N-Pad20)") (class "Default")
      (node (ref "DD7") (pin "20") (pinfunction "MIC_N_20") (pintype "passive"))
    )
    (net (code "126") (name "unconnected-(DD7-MIC_P-Pad19)") (class "Default")
      (node (ref "DD7") (pin "19") (pinfunction "MIC_P_19") (pintype "passive"))
    )
    (net (code "127") (name "unconnected-(DD7-NRESET-Pad16)") (class "Default")
      (node (ref "DD7") (pin "16") (pinfunction "NRESET_16") (pintype "passive"))
    )
    (net (code "128") (name "unconnected-(DD7-PWM1-Pad35)") (class "Default")
      (node (ref "DD7") (pin "35") (pinfunction "PWM1_35") (pintype "passive"))
    )
    (net (code "129") (name "unconnected-(DD7-PWM2-Pad36)") (class "Default")
      (node (ref "DD7") (pin "36") (pinfunction "PWM2_36") (pintype "passive"))
    )
    (net (code "130") (name "unconnected-(DD7-PWRKEY_OUT-Pad2)") (class "Default")
      (node (ref "DD7") (pin "2") (pinfunction "PWRKEY_OUT_2") (pintype "passive"))
    )
    (net (code "131") (name "unconnected-(DD7-RI-Pad4)") (class "Default")
      (node (ref "DD7") (pin "4") (pinfunction "RI_4") (pintype "passive"))
    )
    (net (code "132") (name "unconnected-(DD7-RTS-Pad8)") (class "Default")
      (node (ref "DD7") (pin "8") (pinfunction "RTS_8") (pintype "passive"))
    )
    (net (code "133") (name "unconnected-(DD7-SCL-Pad38)") (class "Default")
      (node (ref "DD7") (pin "38") (pinfunction "SCL_38") (pintype "passive"))
    )
    (net (code "134") (name "unconnected-(DD7-SDA-Pad37)") (class "Default")
      (node (ref "DD7") (pin "37") (pinfunction "SDA_37") (pintype "passive"))
    )
    (net (code "135") (name "unconnected-(DD7-SIM_PRESENCE-Pad34)") (class "Default")
      (node (ref "DD7") (pin "34") (pinfunction "SIM_PRESENCE_34") (pintype "passive"))
    )
    (net (code "136") (name "unconnected-(DD7-SIM_RST-Pad33)") (class "Default")
      (node (ref "DD7") (pin "33") (pinfunction "SIM_RST_33") (pintype "passive"))
    )
    (net (code "137") (name "unconnected-(DD7-VDD_EXT-Pad15)") (class "Default")
      (node (ref "DD7") (pin "15") (pinfunction "VDD_EXT_15") (pintype "passive"))
    )
    (net (code "138") (name "unconnected-(DD8-*INT-Pad13)") (class "Default")
      (node (ref "DD8") (pin "13") (pinfunction "*INT_13") (pintype "passive"))
    )
    (net (code "139") (name "unconnected-(DD8-GND-Pad8)") (class "Default")
      (node (ref "DD8") (pin "8") (pinfunction "GND_8") (pintype "passive"))
    )
    (net (code "140") (name "unconnected-(XS2-D0-Pad7)") (class "Default")
      (node (ref "XS2") (pin "7") (pinfunction "D0_7") (pintype "passive"))
    )
    (net (code "141") (name "unconnected-(XS2-D1-Pad8)") (class "Default")
      (node (ref "XS2") (pin "8") (pinfunction "D1_8") (pintype "passive"))
    )
    (net (code "142") (name "unconnected-(XS2-D2-Pad9)") (class "Default")
      (node (ref "XS2") (pin "9") (pinfunction "D2_9") (pintype "passive"))
    )
    (net (code "143") (name "unconnected-(XS2-VO-Pad3)") (class "Default")
      (node (ref "XS2") (pin "3") (pinfunction "VO_3") (pintype "passive"))
    )
    (net (code "144") (name "unconnected-(XS4-D1-Pad8)") (class "Default")
      (node (ref "XS4") (pin "8") (pinfunction "D1_8") (pintype "passive"))
    )
    (net (code "145") (name "unconnected-(XS8-RST-Pad2)") (class "Default")
      (node (ref "XS8") (pin "2") (pinfunction "RST_2") (pintype "passive"))
    )
    (net (code "146") (name "unconnected-(XS8-VPP-Pad5)") (class "Default")
      (node (ref "XS8") (pin "5") (pinfunction "VPP_5") (pintype "power_in"))
    )
  )
)
